# Boost_converter.net
KiCad netlist of a schematic drawn in EAGLE
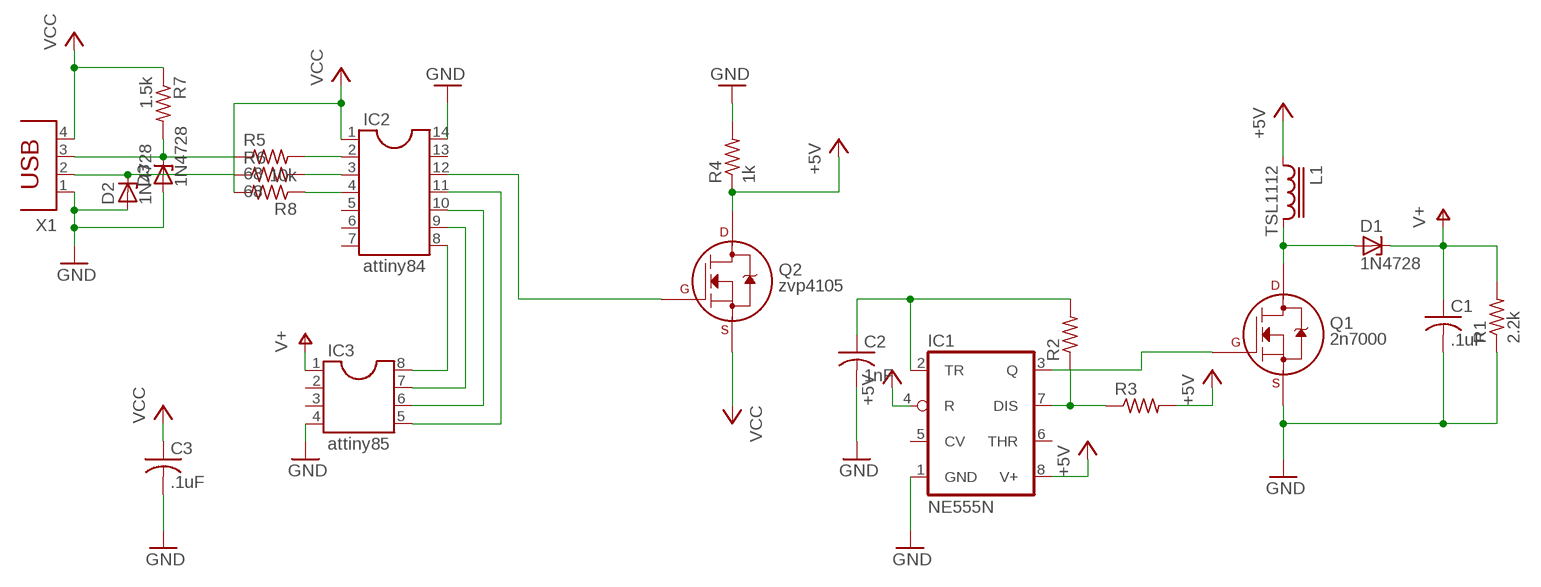
[diagram p0: schematic, sheet 1]

(export (version "E")
  (design (tool "Eeschema 10.0.6"))
  (components
    (comp (ref "C1")
      (value ".1uF")
      (footprint "eagle-import:C025-024X044")
      (libsource (lib "eagle-import") (part "C-US025-024X044"))
    )
    (comp (ref "C2")
      (value "1nF")
      (footprint "eagle-import:C025-024X044")
      (libsource (lib "eagle-import") (part "C-US025-024X044"))
    )
    (comp (ref "C3")
      (value ".1uF")
      (footprint "eagle-import:C025-024X044")
      (libsource (lib "eagle-import") (part "C-US025-024X044"))
    )
    (comp (ref "D1")
      (value "1N4728")
      (footprint "eagle-import:DO41Z10")
      (libsource (lib "eagle-import") (part "1N4728"))
    )
    (comp (ref "D2")
      (value "1N4728")
      (footprint "eagle-import:DO41Z10")
      (libsource (lib "eagle-import") (part "1N4728"))
    )
    (comp (ref "D3")
      (value "1N4728")
      (footprint "eagle-import:DO41Z10")
      (libsource (lib "eagle-import") (part "1N4728"))
    )
    (comp (ref "IC1")
      (value "NE555N")
      (footprint "eagle-import:DIL08-ROUND")
      (libsource (lib "eagle-import") (part "555NNE"))
    )
    (comp (ref "IC2")
      (value "attiny84")
      (footprint "eagle-import:DIL14")
      (libsource (lib "eagle-import") (part "DIL14"))
    )
    (comp (ref "IC3")
      (value "attiny85")
      (footprint "eagle-import:SOCKET-08")
      (libsource (lib "eagle-import") (part "DIL8S"))
    )
    (comp (ref "L1")
      (value "TSL1112")
      (footprint "eagle-import:TSL1112")
      (libsource (lib "eagle-import") (part "TSL1112"))
    )
    (comp (ref "Q1")
      (value "2n7000")
      (footprint "eagle-import:TO-92")
      (libsource (lib "eagle-import") (part "2N700_TO920"))
    )
    (comp (ref "Q2")
      (value "zvp4105")
      (footprint "eagle-import:TO-92")
      (libsource (lib "eagle-import") (part "2N700_TO920"))
    )
    (comp (ref "R1")
      (value "2.2k")
      (footprint "eagle-import:0204_7")
      (libsource (lib "eagle-import") (part "R-US_0204/7"))
    )
    (comp (ref "R2")
      (value "R-US_0204/7")
      (footprint "eagle-import:0204_7")
      (libsource (lib "eagle-import") (part "R-US_0204/7"))
    )
    (comp (ref "R3")
      (value "R-US_0204/7")
      (footprint "eagle-import:0204_7")
      (libsource (lib "eagle-import") (part "R-US_0204/7"))
    )
    (comp (ref "R4")
      (value "1k")
      (footprint "eagle-import:0204_7")
      (libsource (lib "eagle-import") (part "R-US_0204/7"))
    )
    (comp (ref "R5")
      (value "68")
      (footprint "eagle-import:0204_7")
      (libsource (lib "eagle-import") (part "R-US_0204/7"))
    )
    (comp (ref "R6")
      (value "68")
      (footprint "eagle-import:0204_7")
      (libsource (lib "eagle-import") (part "R-US_0204/7"))
    )
    (comp (ref "R7")
      (value "1.5k")
      (footprint "eagle-import:0204_7")
      (libsource (lib "eagle-import") (part "R-US_0204/7"))
    )
    (comp (ref "R8")
      (value "10k")
      (footprint "eagle-import:0204_7")
      (libsource (lib "eagle-import") (part "R-US_0204/7"))
    )
    (comp (ref "X1")
      (value "PN87520")
      (footprint "eagle-import:PN87520")
      (libsource (lib "eagle-import") (part "PN87520"))
    )
  )
  (nets
    (net (code "1") (name "+5V") (class "Default")
      (node (ref "IC1") (pin "4") (pinfunction "R_4") (pintype "input"))
      (node (ref "IC1") (pin "8") (pinfunction "V+_8") (pintype "power_in"))
      (node (ref "L1") (pin "1") (pinfunction "1_1") (pintype "passive"))
      (node (ref "Q2") (pin "3") (pinfunction "D_3") (pintype "bidirectional"))
      (node (ref "R3") (pin "2") (pinfunction "2_2") (pintype "passive"))
      (node (ref "R4") (pin "1") (pinfunction "1_1") (pintype "passive"))
    )
    (net (code "2") (name "GND") (class "Default")
      (node (ref "C1") (pin "2") (pinfunction "2_2") (pintype "passive"))
      (node (ref "C2") (pin "2") (pinfunction "2_2") (pintype "passive"))
      (node (ref "C3") (pin "2") (pinfunction "2_2") (pintype "passive"))
      (node (ref "D2") (pin "A") (pinfunction "A_A") (pintype "passive"))
      (node (ref "D3") (pin "A") (pinfunction "A_A") (pintype "passive"))
      (node (ref "IC1") (pin "1") (pinfunction "GND_1") (pintype "power_in"))
      (node (ref "IC2") (pin "14") (pinfunction "14_14") (pintype "passive"))
      (node (ref "IC3") (pin "4") (pinfunction "4_4") (pintype "passive"))
      (node (ref "Q1") (pin "1") (pinfunction "S_1") (pintype "bidirectional"))
      (node (ref "R1") (pin "1") (pinfunction "1_1") (pintype "passive"))
      (node (ref "R4") (pin "2") (pinfunction "2_2") (pintype "passive"))
      (node (ref "X1") (pin "1") (pinfunction "1_1") (pintype "passive"))
    )
    (net (code "3") (name "Net-(D2-PadC)") (class "Default")
      (node (ref "D2") (pin "C") (pinfunction "C_C") (pintype "passive"))
      (node (ref "R6") (pin "1") (pinfunction "1_1") (pintype "passive"))
      (node (ref "X1") (pin "2") (pinfunction "2_2") (pintype "passive"))
    )
    (net (code "4") (name "Net-(D3-PadC)") (class "Default")
      (node (ref "D3") (pin "C") (pinfunction "C_C") (pintype "passive"))
      (node (ref "R5") (pin "1") (pinfunction "1_1") (pintype "passive"))
      (node (ref "R7") (pin "2") (pinfunction "2_2") (pintype "passive"))
      (node (ref "X1") (pin "3") (pinfunction "3_3") (pintype "passive"))
    )
    (net (code "5") (name "Net-(IC1-DIS)") (class "Default")
      (node (ref "IC1") (pin "7") (pinfunction "DIS_7") (pintype "input"))
      (node (ref "R2") (pin "1") (pinfunction "1_1") (pintype "passive"))
      (node (ref "R3") (pin "1") (pinfunction "1_1") (pintype "passive"))
    )
    (net (code "6") (name "Net-(IC1-Q)") (class "Default")
      (node (ref "IC1") (pin "3") (pinfunction "Q_3") (pintype "output"))
      (node (ref "Q1") (pin "2") (pinfunction "G_2") (pintype "tri_state"))
    )
    (net (code "7") (name "Net-(IC1-TR)") (class "Default")
      (node (ref "C2") (pin "1") (pinfunction "1_1") (pintype "passive"))
      (node (ref "IC1") (pin "2") (pinfunction "TR_2") (pintype "input"))
      (node (ref "R2") (pin "2") (pinfunction "2_2") (pintype "passive"))
    )
    (net (code "8") (name "Net-(IC2-Pad2)") (class "Default")
      (node (ref "IC2") (pin "2") (pinfunction "2_2") (pintype "passive"))
      (node (ref "R5") (pin "2") (pinfunction "2_2") (pintype "passive"))
    )
    (net (code "9") (name "Net-(IC2-Pad3)") (class "Default")
      (node (ref "IC2") (pin "3") (pinfunction "3_3") (pintype "passive"))
      (node (ref "R6") (pin "2") (pinfunction "2_2") (pintype "passive"))
    )
    (net (code "10") (name "Net-(IC2-Pad4)") (class "Default")
      (node (ref "IC2") (pin "4") (pinfunction "4_4") (pintype "passive"))
      (node (ref "R8") (pin "1") (pinfunction "1_1") (pintype "passive"))
    )
    (net (code "11") (name "Net-(IC2-Pad8)") (class "Default")
      (node (ref "IC2") (pin "8") (pinfunction "8_8") (pintype "passive"))
      (node (ref "IC3") (pin "8") (pinfunction "8_8") (pintype "passive"))
    )
    (net (code "12") (name "Net-(IC2-Pad9)") (class "Default")
      (node (ref "IC2") (pin "9") (pinfunction "9_9") (pintype "passive"))
      (node (ref "IC3") (pin "7") (pinfunction "7_7") (pintype "passive"))
    )
    (net (code "13") (name "Net-(IC2-Pad10)") (class "Default")
      (node (ref "IC2") (pin "10") (pinfunction "10_10") (pintype "passive"))
      (node (ref "IC3") (pin "6") (pinfunction "6_6") (pintype "passive"))
    )
    (net (code "14") (name "Net-(IC2-Pad11)") (class "Default")
      (node (ref "IC2") (pin "11") (pinfunction "11_11") (pintype "passive"))
      (node (ref "IC3") (pin "5") (pinfunction "5_5") (pintype "passive"))
    )
    (net (code "15") (name "Net-(Q1-D)") (class "Default")
      (node (ref "D1") (pin "A") (pinfunction "A_A") (pintype "passive"))
      (node (ref "L1") (pin "2") (pinfunction "2_2") (pintype "passive"))
      (node (ref "Q1") (pin "3") (pinfunction "D_3") (pintype "bidirectional"))
    )
    (net (code "16") (name "Net-(Q2-G)") (class "Default")
      (node (ref "IC2") (pin "12") (pinfunction "12_12") (pintype "passive"))
      (node (ref "Q2") (pin "2") (pinfunction "G_2") (pintype "tri_state"))
    )
    (net (code "17") (name "V+") (class "Default")
      (node (ref "C1") (pin "1") (pinfunction "1_1") (pintype "passive"))
      (node (ref "D1") (pin "C") (pinfunction "C_C") (pintype "passive"))
      (node (ref "IC3") (pin "1") (pinfunction "1_1") (pintype "passive"))
      (node (ref "R1") (pin "2") (pinfunction "2_2") (pintype "passive"))
    )
    (net (code "18") (name "VCC") (class "Default")
      (node (ref "C3") (pin "1") (pinfunction "1_1") (pintype "passive"))
      (node (ref "IC2") (pin "1") (pinfunction "1_1") (pintype "passive"))
      (node (ref "Q2") (pin "1") (pinfunction "S_1") (pintype "bidirectional"))
      (node (ref "R7") (pin "1") (pinfunction "1_1") (pintype "passive"))
      (node (ref "R8") (pin "2") (pinfunction "2_2") (pintype "passive"))
      (node (ref "X1") (pin "4") (pinfunction "4_4") (pintype "passive"))
    )
    (net (code "19") (name "unconnected-(IC1-CV-Pad5)") (class "Default")
      (node (ref "IC1") (pin "5") (pinfunction "CV_5") (pintype "input"))
    )
    (net (code "20") (name "unconnected-(IC1-THR-Pad6)") (class "Default")
      (node (ref "IC1") (pin "6") (pinfunction "THR_6") (pintype "input"))
    )
    (net (code "21") (name "unconnected-(IC2-Pad5)") (class "Default")
      (node (ref "IC2") (pin "5") (pinfunction "5_5") (pintype "passive"))
    )
    (net (code "22") (name "unconnected-(IC2-Pad6)") (class "Default")
      (node (ref "IC2") (pin "6") (pinfunction "6_6") (pintype "passive"))
    )
    (net (code "23") (name "unconnected-(IC2-Pad7)") (class "Default")
      (node (ref "IC2") (pin "7") (pinfunction "7_7") (pintype "passive"))
    )
    (net (code "24") (name "unconnected-(IC2-Pad13)") (class "Default")
      (node (ref "IC2") (pin "13") (pinfunction "13_13") (pintype "passive"))
    )
    (net (code "25") (name "unconnected-(IC3-Pad2)") (class "Default")
      (node (ref "IC3") (pin "2") (pinfunction "2_2") (pintype "passive"))
    )
    (net (code "26") (name "unconnected-(IC3-Pad3)") (class "Default")
      (node (ref "IC3") (pin "3") (pinfunction "3_3") (pintype "passive"))
    )
  )
)
